# Ring_Switch_PCB_FFC.net
KiCad netlist of a schematic drawn in EAGLE
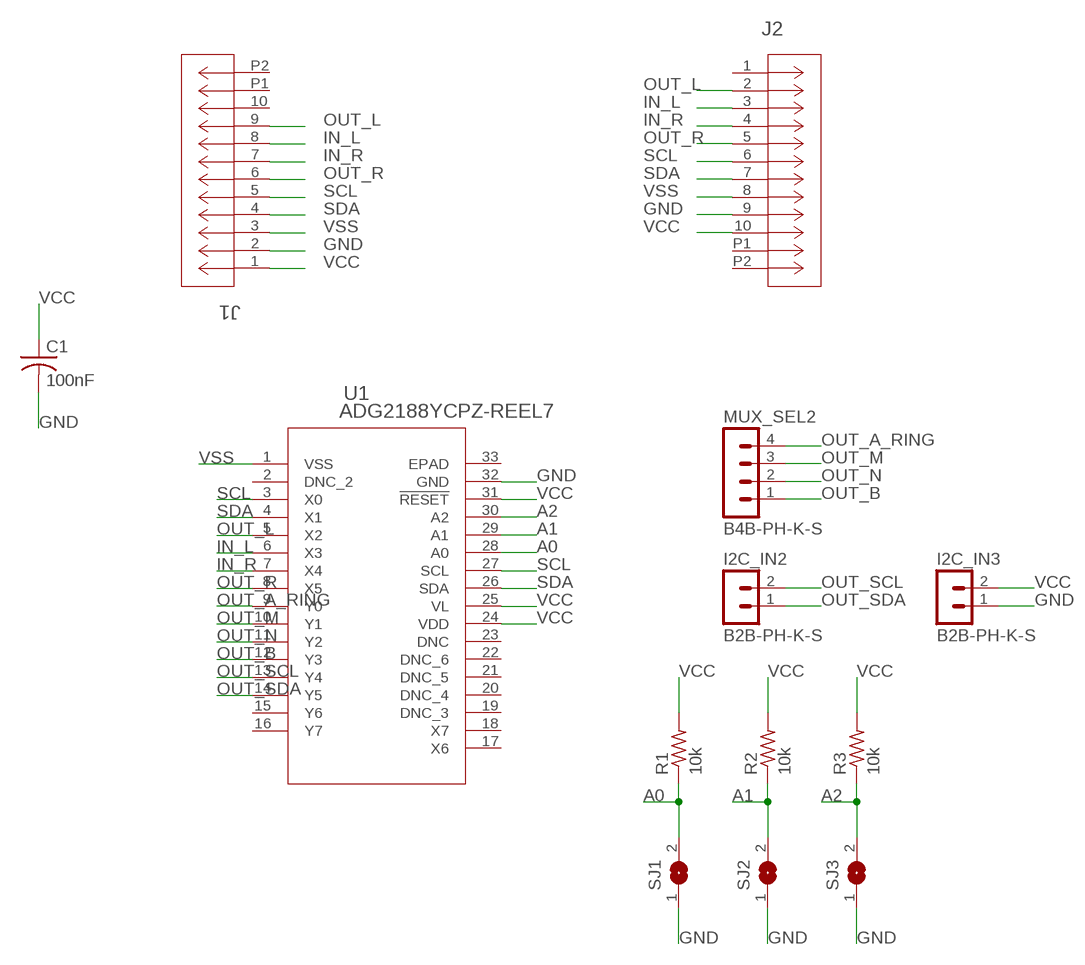
[diagram p0: schematic, sheet 1]

(export (version "E")
  (design (tool "Eeschema 10.0.6"))
  (components
    (comp (ref "C1")
      (value "100nF")
      (footprint "eagle-import:C0603")
      (libsource (lib "eagle-import") (part "C-USC0603"))
    )
    (comp (ref "I2C_IN2")
      (value "B2B-PH-K-S")
      (footprint "eagle-import:B2B-PH-K-S")
      (libsource (lib "eagle-import") (part "B2B-PH-K-S"))
    )
    (comp (ref "I2C_IN3")
      (value "B2B-PH-K-S")
      (footprint "eagle-import:B2B-PH-K-S")
      (libsource (lib "eagle-import") (part "B2B-PH-K-S"))
    )
    (comp (ref "J1")
      (value "522711079")
      (footprint "eagle-import:CON_522711079_MOL")
      (fields (field (name "COPYRIGHT") "Copyright (C) 2023 Ultra Librarian. All rights reserved."))
      (libsource (lib "eagle-import") (part "522711079"))
    )
    (comp (ref "J2")
      (value "522711079")
      (footprint "eagle-import:CON_522711079_MOL")
      (fields (field (name "COPYRIGHT") "Copyright (C) 2023 Ultra Librarian. All rights reserved."))
      (libsource (lib "eagle-import") (part "522711079"))
    )
    (comp (ref "MUX_SEL2")
      (value "B4B-PH-K-S")
      (footprint "eagle-import:B4B-PH-K-S")
      (libsource (lib "eagle-import") (part "B4B-PH-K-S"))
    )
    (comp (ref "R1")
      (value "10k")
      (footprint "eagle-import:R0603")
      (libsource (lib "eagle-import") (part "R-US_R0603"))
    )
    (comp (ref "R2")
      (value "10k")
      (footprint "eagle-import:R0603")
      (libsource (lib "eagle-import") (part "R-US_R0603"))
    )
    (comp (ref "R3")
      (value "10k")
      (footprint "eagle-import:R0603")
      (libsource (lib "eagle-import") (part "R-US_R0603"))
    )
    (comp (ref "SJ1") (value "SJ") (footprint "eagle-import:SJ") (libsource (lib "eagle-import") (part "SJ")))
    (comp (ref "SJ2") (value "SJ") (footprint "eagle-import:SJ") (libsource (lib "eagle-import") (part "SJ")))
    (comp (ref "SJ3") (value "SJ") (footprint "eagle-import:SJ") (libsource (lib "eagle-import") (part "SJ")))
    (comp (ref "U1")
      (value "ADG2188YCPZ-REEL7")
      (footprint "eagle-import:CP_32_7_ADI")
      (fields (field (name "COPYRIGHT") "Copyright (C) 2016 Accelerated Designs. All rights reserved"))
      (libsource (lib "eagle-import") (part "ADG2188YCPZ-REEL7"))
    )
  )
  (nets
    (net (code "1") (name "/A0") (class "Default")
      (node (ref "R1") (pin "1") (pinfunction "1_1") (pintype "passive"))
      (node (ref "SJ1") (pin "2") (pinfunction "2_2") (pintype "passive"))
      (node (ref "U1") (pin "28") (pinfunction "A0_28") (pintype "bidirectional"))
    )
    (net (code "2") (name "/A1") (class "Default")
      (node (ref "R2") (pin "1") (pinfunction "1_1") (pintype "passive"))
      (node (ref "SJ2") (pin "2") (pinfunction "2_2") (pintype "passive"))
      (node (ref "U1") (pin "29") (pinfunction "A1_29") (pintype "bidirectional"))
    )
    (net (code "3") (name "/A2") (class "Default")
      (node (ref "R3") (pin "1") (pinfunction "1_1") (pintype "passive"))
      (node (ref "SJ3") (pin "2") (pinfunction "2_2") (pintype "passive"))
      (node (ref "U1") (pin "30") (pinfunction "A2_30") (pintype "bidirectional"))
    )
    (net (code "4") (name "/GND") (class "Default")
      (node (ref "C1") (pin "2") (pinfunction "2_2") (pintype "passive"))
      (node (ref "I2C_IN3") (pin "1") (pinfunction "1_1") (pintype "passive"))
      (node (ref "J1") (pin "2") (pinfunction "2_2") (pintype "passive"))
      (node (ref "J2") (pin "9") (pinfunction "9_9") (pintype "passive"))
      (node (ref "SJ1") (pin "1") (pinfunction "1_1") (pintype "passive"))
      (node (ref "SJ2") (pin "1") (pinfunction "1_1") (pintype "passive"))
      (node (ref "SJ3") (pin "1") (pinfunction "1_1") (pintype "passive"))
      (node (ref "U1") (pin "32") (pinfunction "GND_32") (pintype "passive"))
    )
    (net (code "5") (name "/IN_L") (class "Default")
      (node (ref "J1") (pin "8") (pinfunction "8_8") (pintype "passive"))
      (node (ref "J2") (pin "3") (pinfunction "3_3") (pintype "passive"))
      (node (ref "U1") (pin "6") (pinfunction "X3_6") (pintype "bidirectional"))
    )
    (net (code "6") (name "/IN_R") (class "Default")
      (node (ref "J1") (pin "7") (pinfunction "7_7") (pintype "passive"))
      (node (ref "J2") (pin "4") (pinfunction "4_4") (pintype "passive"))
      (node (ref "U1") (pin "7") (pinfunction "X4_7") (pintype "bidirectional"))
    )
    (net (code "7") (name "/OUT_A_RING") (class "Default")
      (node (ref "MUX_SEL2") (pin "4") (pinfunction "4_4") (pintype "passive"))
      (node (ref "U1") (pin "9") (pinfunction "Y0_9") (pintype "bidirectional"))
    )
    (net (code "8") (name "/OUT_B") (class "Default")
      (node (ref "MUX_SEL2") (pin "1") (pinfunction "1_1") (pintype "passive"))
      (node (ref "U1") (pin "12") (pinfunction "Y3_12") (pintype "bidirectional"))
    )
    (net (code "9") (name "/OUT_L") (class "Default")
      (node (ref "J1") (pin "9") (pinfunction "9_9") (pintype "passive"))
      (node (ref "J2") (pin "2") (pinfunction "2_2") (pintype "passive"))
      (node (ref "U1") (pin "5") (pinfunction "X2_5") (pintype "bidirectional"))
    )
    (net (code "10") (name "/OUT_M") (class "Default")
      (node (ref "MUX_SEL2") (pin "3") (pinfunction "3_3") (pintype "passive"))
      (node (ref "U1") (pin "10") (pinfunction "Y1_10") (pintype "bidirectional"))
    )
    (net (code "11") (name "/OUT_N") (class "Default")
      (node (ref "MUX_SEL2") (pin "2") (pinfunction "2_2") (pintype "passive"))
      (node (ref "U1") (pin "11") (pinfunction "Y2_11") (pintype "bidirectional"))
    )
    (net (code "12") (name "/OUT_R") (class "Default")
      (node (ref "J1") (pin "6") (pinfunction "6_6") (pintype "passive"))
      (node (ref "J2") (pin "5") (pinfunction "5_5") (pintype "passive"))
      (node (ref "U1") (pin "8") (pinfunction "X5_8") (pintype "bidirectional"))
    )
    (net (code "13") (name "/OUT_SCL") (class "Default")
      (node (ref "I2C_IN2") (pin "2") (pinfunction "2_2") (pintype "passive"))
      (node (ref "U1") (pin "13") (pinfunction "Y4_13") (pintype "bidirectional"))
    )
    (net (code "14") (name "/OUT_SDA") (class "Default")
      (node (ref "I2C_IN2") (pin "1") (pinfunction "1_1") (pintype "passive"))
      (node (ref "U1") (pin "14") (pinfunction "Y5_14") (pintype "bidirectional"))
    )
    (net (code "15") (name "/SCL") (class "Default")
      (node (ref "J1") (pin "5") (pinfunction "5_5") (pintype "passive"))
      (node (ref "J2") (pin "6") (pinfunction "6_6") (pintype "passive"))
      (node (ref "U1") (pin "27") (pinfunction "SCL_27") (pintype "input"))
      (node (ref "U1") (pin "3") (pinfunction "X0_3") (pintype "bidirectional"))
    )
    (net (code "16") (name "/SDA") (class "Default")
      (node (ref "J1") (pin "4") (pinfunction "4_4") (pintype "passive"))
      (node (ref "J2") (pin "7") (pinfunction "7_7") (pintype "passive"))
      (node (ref "U1") (pin "26") (pinfunction "SDA_26") (pintype "bidirectional"))
      (node (ref "U1") (pin "4") (pinfunction "X1_4") (pintype "bidirectional"))
    )
    (net (code "17") (name "/VCC") (class "Default")
      (node (ref "C1") (pin "1") (pinfunction "1_1") (pintype "passive"))
      (node (ref "I2C_IN3") (pin "2") (pinfunction "2_2") (pintype "passive"))
      (node (ref "J1") (pin "1") (pinfunction "1_1") (pintype "passive"))
      (node (ref "J2") (pin "10") (pinfunction "10_10") (pintype "passive"))
      (node (ref "R1") (pin "2") (pinfunction "2_2") (pintype "passive"))
      (node (ref "R2") (pin "2") (pinfunction "2_2") (pintype "passive"))
      (node (ref "R3") (pin "2") (pinfunction "2_2") (pintype "passive"))
      (node (ref "U1") (pin "24") (pinfunction "VDD_24") (pintype "input"))
      (node (ref "U1") (pin "25") (pinfunction "VL_25") (pintype "input"))
      (node (ref "U1") (pin "31") (pinfunction "~{RESET}_31") (pintype "input"))
    )
    (net (code "18") (name "/VSS") (class "Default")
      (node (ref "J1") (pin "3") (pinfunction "3_3") (pintype "passive"))
      (node (ref "J2") (pin "8") (pinfunction "8_8") (pintype "passive"))
      (node (ref "U1") (pin "1") (pinfunction "VSS_1") (pintype "passive"))
    )
    (net (code "19") (name "unconnected-(J1-Pad10)") (class "Default")
      (node (ref "J1") (pin "10") (pinfunction "10_10") (pintype "passive"))
    )
    (net (code "20") (name "unconnected-(J1-PadP1)") (class "Default")
      (node (ref "J1") (pin "P1") (pinfunction "P1_P1") (pintype "passive"))
    )
    (net (code "21") (name "unconnected-(J1-PadP2)") (class "Default")
      (node (ref "J1") (pin "P2") (pinfunction "P2_P2") (pintype "passive"))
    )
    (net (code "22") (name "unconnected-(J2-Pad1)") (class "Default")
      (node (ref "J2") (pin "1") (pinfunction "1_1") (pintype "passive"))
    )
    (net (code "23") (name "unconnected-(J2-PadP1)") (class "Default")
      (node (ref "J2") (pin "P1") (pinfunction "P1_P1") (pintype "passive"))
    )
    (net (code "24") (name "unconnected-(J2-PadP2)") (class "Default")
      (node (ref "J2") (pin "P2") (pinfunction "P2_P2") (pintype "passive"))
    )
    (net (code "25") (name "unconnected-(U1-DNC-Pad23)") (class "Default")
      (node (ref "U1") (pin "23") (pinfunction "DNC_23") (pintype "no_connect"))
    )
    (net (code "26") (name "unconnected-(U1-DNC_2-Pad2)") (class "Default")
      (node (ref "U1") (pin "2") (pinfunction "DNC_2_2") (pintype "no_connect"))
    )
    (net (code "27") (name "unconnected-(U1-DNC_3-Pad19)") (class "Default")
      (node (ref "U1") (pin "19") (pinfunction "DNC_3_19") (pintype "no_connect"))
    )
    (net (code "28") (name "unconnected-(U1-DNC_4-Pad20)") (class "Default")
      (node (ref "U1") (pin "20") (pinfunction "DNC_4_20") (pintype "no_connect"))
    )
    (net (code "29") (name "unconnected-(U1-DNC_5-Pad21)") (class "Default")
      (node (ref "U1") (pin "21") (pinfunction "DNC_5_21") (pintype "no_connect"))
    )
    (net (code "30") (name "unconnected-(U1-DNC_6-Pad22)") (class "Default")
      (node (ref "U1") (pin "22") (pinfunction "DNC_6_22") (pintype "no_connect"))
    )
    (net (code "31") (name "unconnected-(U1-EPAD-Pad33)") (class "Default")
      (node (ref "U1") (pin "33") (pinfunction "EPAD_33") (pintype "passive"))
    )
    (net (code "32") (name "unconnected-(U1-X6-Pad17)") (class "Default")
      (node (ref "U1") (pin "17") (pinfunction "X6_17") (pintype "bidirectional"))
    )
    (net (code "33") (name "unconnected-(U1-X7-Pad18)") (class "Default")
      (node (ref "U1") (pin "18") (pinfunction "X7_18") (pintype "bidirectional"))
    )
    (net (code "34") (name "unconnected-(U1-Y6-Pad15)") (class "Default")
      (node (ref "U1") (pin "15") (pinfunction "Y6_15") (pintype "bidirectional"))
    )
    (net (code "35") (name "unconnected-(U1-Y7-Pad16)") (class "Default")
      (node (ref "U1") (pin "16") (pinfunction "Y7_16") (pintype "bidirectional"))
    )
  )
)
